# SCH_USB-Hub_2024-12-28.net
KiCad netlist of a schematic drawn in EasyEDA
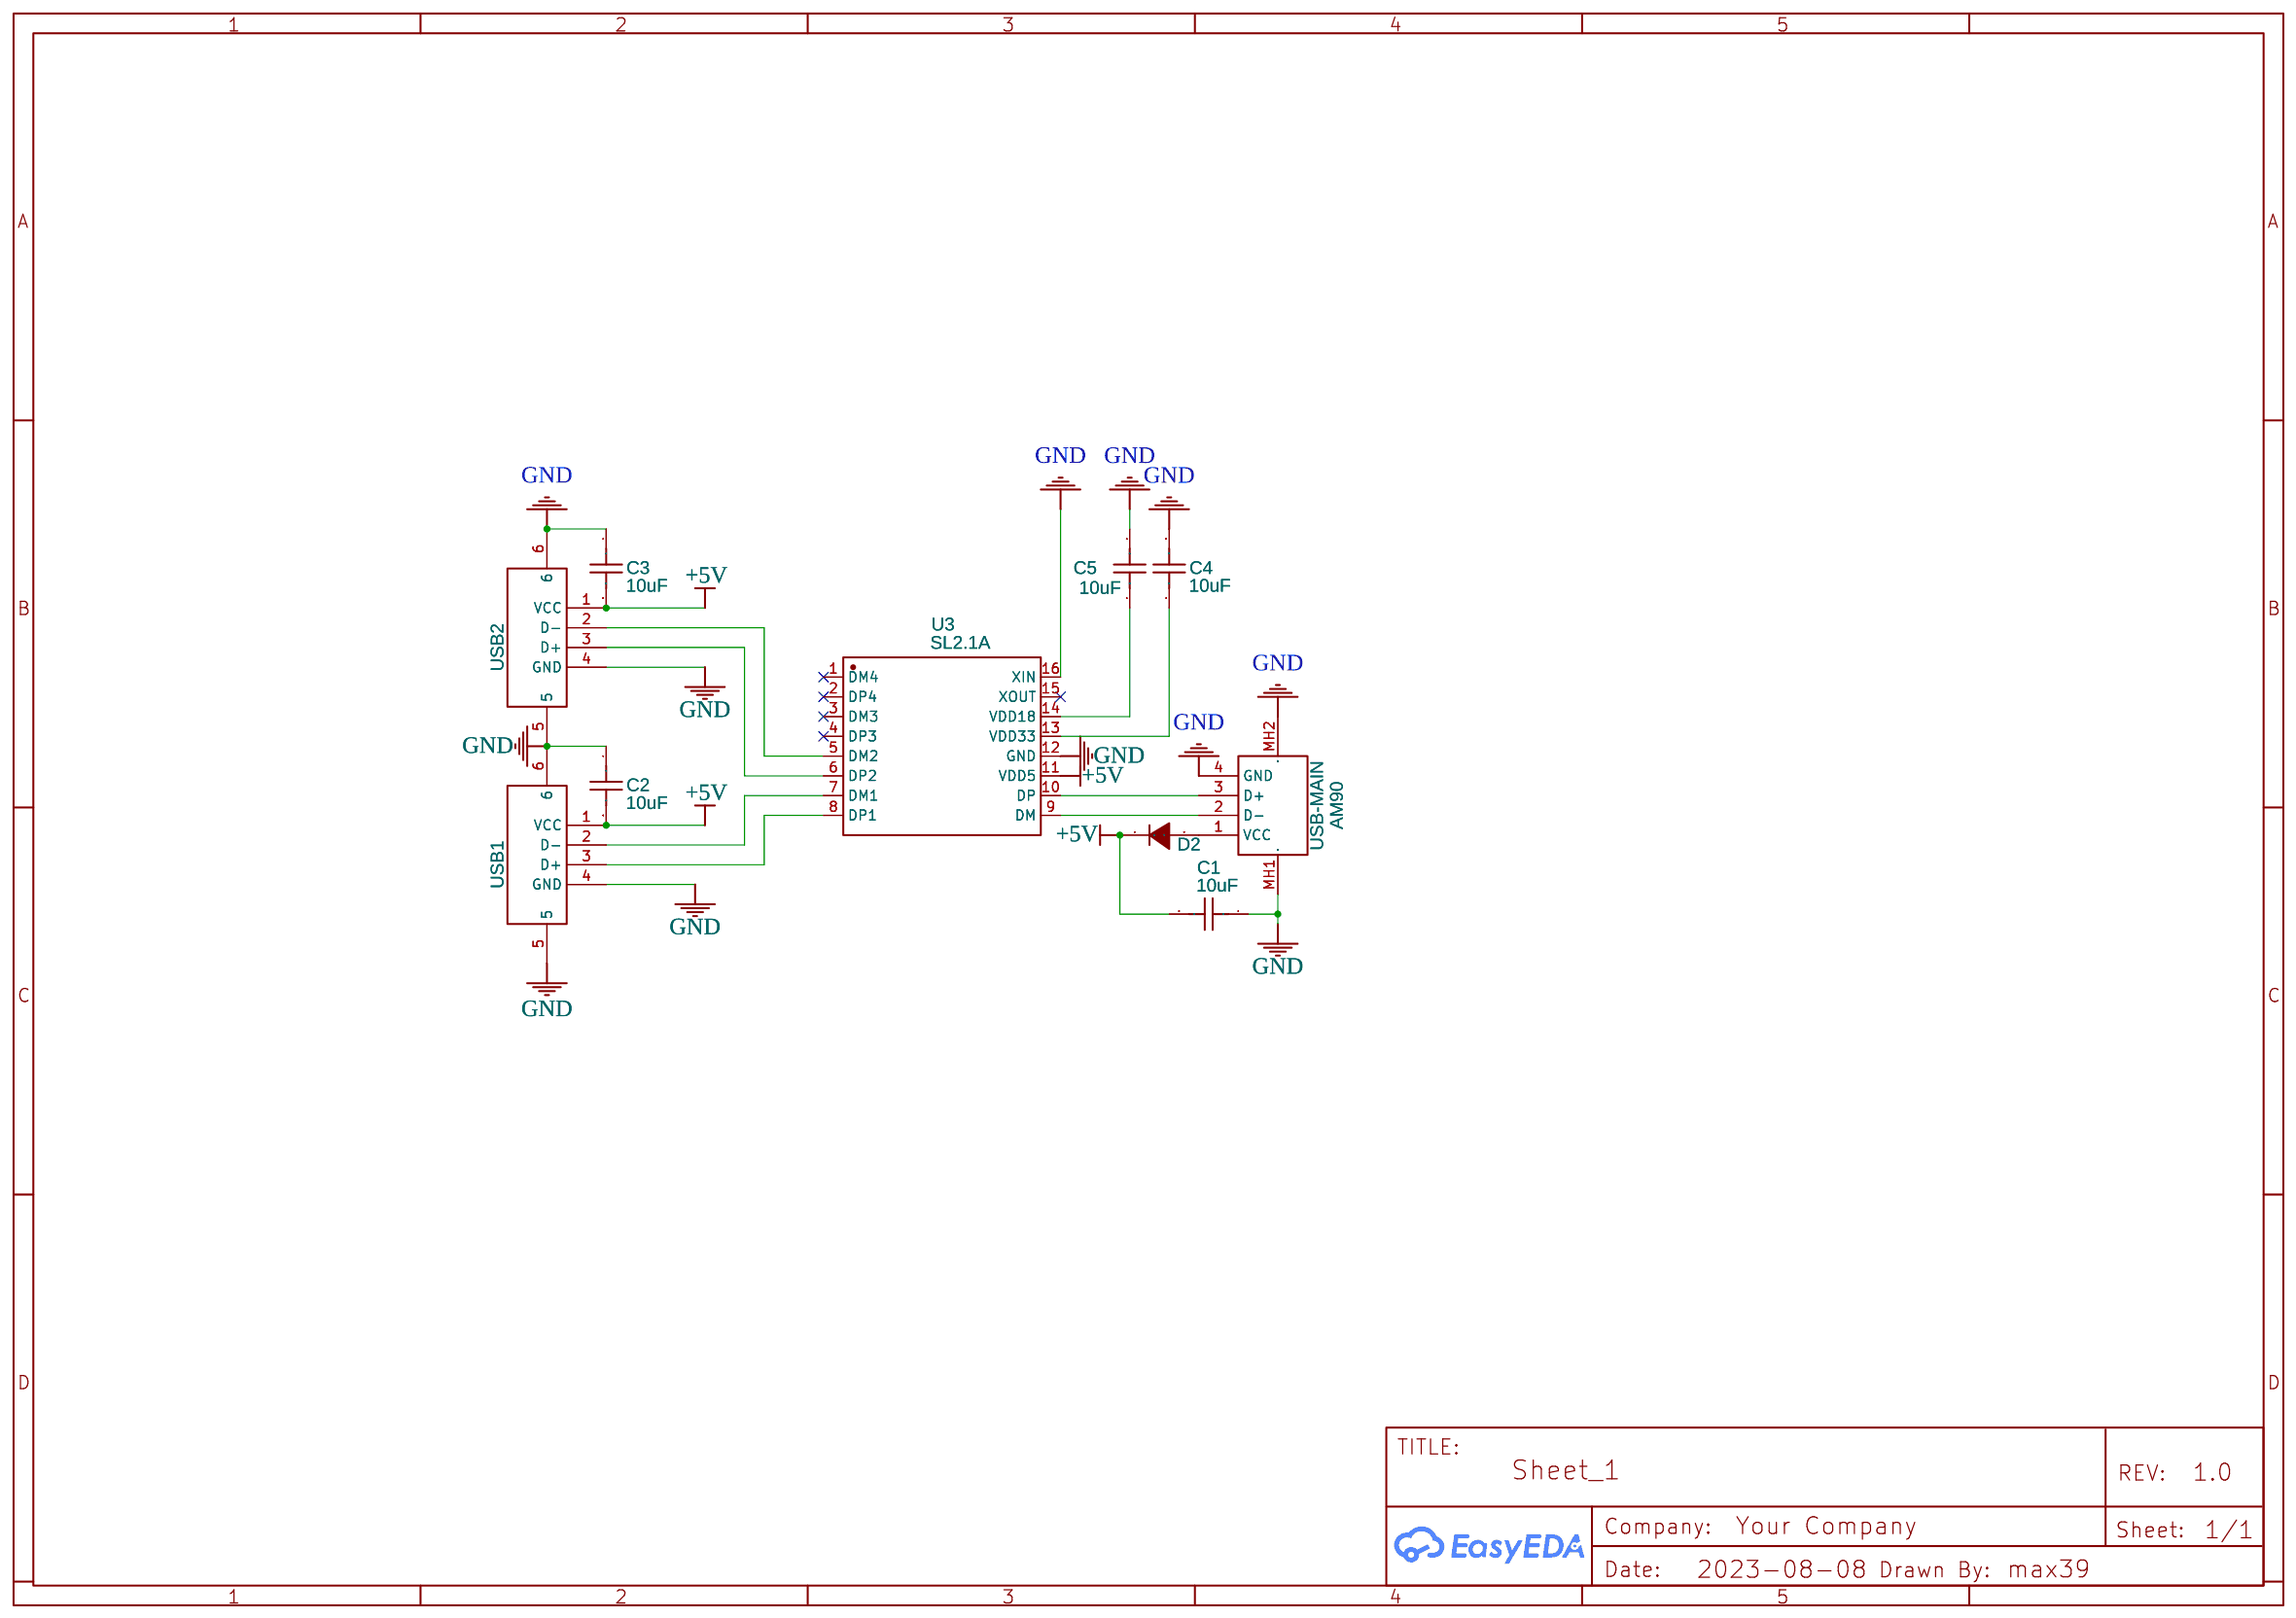
[diagram p0: schematic sheet]

(export (version "E")
  (design (tool "Eeschema 10.0.6"))
  (components
    (comp (ref "C1")
      (value "10uF")
      (fields
        (field (name "Manufacturer Part") "CL10A106KP8NNNC")
        (field (name "Manufacturer") "SAMSUNG(三星)")
      )
      (libsource (lib "") (part "CL10A106KP8NNNC_1"))
    )
    (comp (ref "C2")
      (value "10uF")
      (fields
        (field (name "Manufacturer Part") "CL10A106KP8NNNC")
        (field (name "Manufacturer") "SAMSUNG(三星)")
      )
      (libsource (lib "") (part "CL10A106KP8NNNC"))
    )
    (comp (ref "C3")
      (value "10uF")
      (fields
        (field (name "Manufacturer Part") "CL10A106KP8NNNC")
        (field (name "Manufacturer") "SAMSUNG(三星)")
      )
      (libsource (lib "") (part "CL10A106KP8NNNC"))
    )
    (comp (ref "C4") (value "10uF") (libsource (lib "") (part "C_0603_US")))
    (comp (ref "C5") (value "10uF") (libsource (lib "") (part "C_0603_US")))
    (comp (ref "D2")
      (value "NSR0320MW2T1G")
      (fields (field (name "Manufacturer") "onsemi(安森美)"))
      (libsource (lib "") (part "NSR0320MW2T1G"))
    )
    (comp (ref "U3")
      (value "SL2.1A")
      (fields (field (name "Manufacturer") "CoreChips(和芯润德)"))
      (libsource (lib "") (part "SL2.1A"))
    )
    (comp (ref "USB-MAIN") (value "AM90") (libsource (lib "") (part "AM90")))
    (comp (ref "USB1")
      (value "USB-AF-90-14.4X13.6-H7.0-DIP")
      (fields (field (name "Manufacturer Part") "903-131A1011D10100") (field (name "Manufacturer") "精拓金"))
      (libsource (lib "") (part "USB-AF-90-14.4X13.6-H7.0-DIP"))
    )
    (comp (ref "USB2")
      (value "USB-AF-90-14.4X13.6-H7.0-DIP")
      (fields (field (name "Manufacturer Part") "903-131A1011D10100") (field (name "Manufacturer") "精拓金"))
      (libsource (lib "") (part "USB-AF-90-14.4X13.6-H7.0-DIP"))
    )
  )
  (nets
    (net (code "1") (name "+5V") (class "Default")
      (node (ref "C1") (pin "2") (pinfunction "2_2") (pintype "unspecified"))
      (node (ref "C2") (pin "2") (pinfunction "2_2") (pintype "unspecified"))
      (node (ref "C3") (pin "2") (pinfunction "2_2") (pintype "unspecified"))
      (node (ref "D2") (pin "1") (pinfunction "C_1") (pintype "unspecified"))
      (node (ref "U3") (pin "11") (pinfunction "VDD5_11") (pintype "unspecified"))
      (node (ref "USB1") (pin "1") (pinfunction "VCC_1") (pintype "unspecified"))
      (node (ref "USB2") (pin "1") (pinfunction "VCC_1") (pintype "unspecified"))
    )
    (net (code "2") (name "GND") (class "Default")
      (node (ref "C1") (pin "1") (pinfunction "1_1") (pintype "unspecified"))
      (node (ref "C2") (pin "1") (pinfunction "1_1") (pintype "unspecified"))
      (node (ref "C3") (pin "1") (pinfunction "1_1") (pintype "unspecified"))
      (node (ref "C4") (pin "2") (pinfunction "2_2") (pintype "unspecified"))
      (node (ref "C5") (pin "2") (pinfunction "2_2") (pintype "unspecified"))
      (node (ref "U3") (pin "12") (pinfunction "GND_12") (pintype "unspecified"))
      (node (ref "U3") (pin "16") (pinfunction "XIN_16") (pintype "unspecified"))
      (node (ref "USB-MAIN") (pin "4") (pinfunction "GND_4") (pintype "input"))
      (node (ref "USB-MAIN") (pin "MH1") (pinfunction "MH1_MH1") (pintype "unspecified"))
      (node (ref "USB-MAIN") (pin "MH2") (pinfunction "MH2_MH2") (pintype "unspecified"))
      (node (ref "USB1") (pin "4") (pinfunction "GND_4") (pintype "unspecified"))
      (node (ref "USB1") (pin "5") (pinfunction "5_5") (pintype "unspecified"))
      (node (ref "USB1") (pin "6") (pinfunction "6_6") (pintype "unspecified"))
      (node (ref "USB2") (pin "4") (pinfunction "GND_4") (pintype "unspecified"))
      (node (ref "USB2") (pin "5") (pinfunction "5_5") (pintype "unspecified"))
      (node (ref "USB2") (pin "6") (pinfunction "6_6") (pintype "unspecified"))
    )
    (net (code "3") (name "Net-(D2-A)") (class "Default")
      (node (ref "D2") (pin "2") (pinfunction "A_2") (pintype "unspecified"))
      (node (ref "USB-MAIN") (pin "1") (pinfunction "VCC_1") (pintype "input"))
    )
    (net (code "4") (name "Net-(U3-DM)") (class "Default")
      (node (ref "U3") (pin "9") (pinfunction "DM_9") (pintype "unspecified"))
      (node (ref "USB-MAIN") (pin "2") (pinfunction "D-_2") (pintype "input"))
    )
    (net (code "5") (name "Net-(U3-DM1)") (class "Default")
      (node (ref "U3") (pin "7") (pinfunction "DM1_7") (pintype "unspecified"))
      (node (ref "USB1") (pin "2") (pinfunction "D-_2") (pintype "unspecified"))
    )
    (net (code "6") (name "Net-(U3-DM2)") (class "Default")
      (node (ref "U3") (pin "5") (pinfunction "DM2_5") (pintype "unspecified"))
      (node (ref "USB2") (pin "2") (pinfunction "D-_2") (pintype "unspecified"))
    )
    (net (code "7") (name "Net-(U3-DP)") (class "Default")
      (node (ref "U3") (pin "10") (pinfunction "DP_10") (pintype "unspecified"))
      (node (ref "USB-MAIN") (pin "3") (pinfunction "D+_3") (pintype "input"))
    )
    (net (code "8") (name "Net-(U3-DP1)") (class "Default")
      (node (ref "U3") (pin "8") (pinfunction "DP1_8") (pintype "unspecified"))
      (node (ref "USB1") (pin "3") (pinfunction "D+_3") (pintype "unspecified"))
    )
    (net (code "9") (name "Net-(U3-DP2)") (class "Default")
      (node (ref "U3") (pin "6") (pinfunction "DP2_6") (pintype "unspecified"))
      (node (ref "USB2") (pin "3") (pinfunction "D+_3") (pintype "unspecified"))
    )
    (net (code "10") (name "Net-(U3-VDD18)") (class "Default")
      (node (ref "C5") (pin "1") (pinfunction "1_1") (pintype "unspecified"))
      (node (ref "U3") (pin "14") (pinfunction "VDD18_14") (pintype "unspecified"))
    )
    (net (code "11") (name "Net-(U3-VDD33)") (class "Default")
      (node (ref "C4") (pin "1") (pinfunction "1_1") (pintype "unspecified"))
      (node (ref "U3") (pin "13") (pinfunction "VDD33_13") (pintype "unspecified"))
    )
    (net (code "12") (name "unconnected-(U3-DM3-Pad3)") (class "Default")
      (node (ref "U3") (pin "3") (pinfunction "DM3_3") (pintype "unspecified+no_connect"))
    )
    (net (code "13") (name "unconnected-(U3-DM4-Pad1)") (class "Default")
      (node (ref "U3") (pin "1") (pinfunction "DM4_1") (pintype "unspecified+no_connect"))
    )
    (net (code "14") (name "unconnected-(U3-DP3-Pad4)") (class "Default")
      (node (ref "U3") (pin "4") (pinfunction "DP3_4") (pintype "unspecified+no_connect"))
    )
    (net (code "15") (name "unconnected-(U3-DP4-Pad2)") (class "Default")
      (node (ref "U3") (pin "2") (pinfunction "DP4_2") (pintype "unspecified+no_connect"))
    )
    (net (code "16") (name "unconnected-(U3-XOUT-Pad15)") (class "Default")
      (node (ref "U3") (pin "15") (pinfunction "XOUT_15") (pintype "unspecified+no_connect"))
    )
  )
)
